# rom.net
KiCad netlist of a schematic drawn in EAGLE
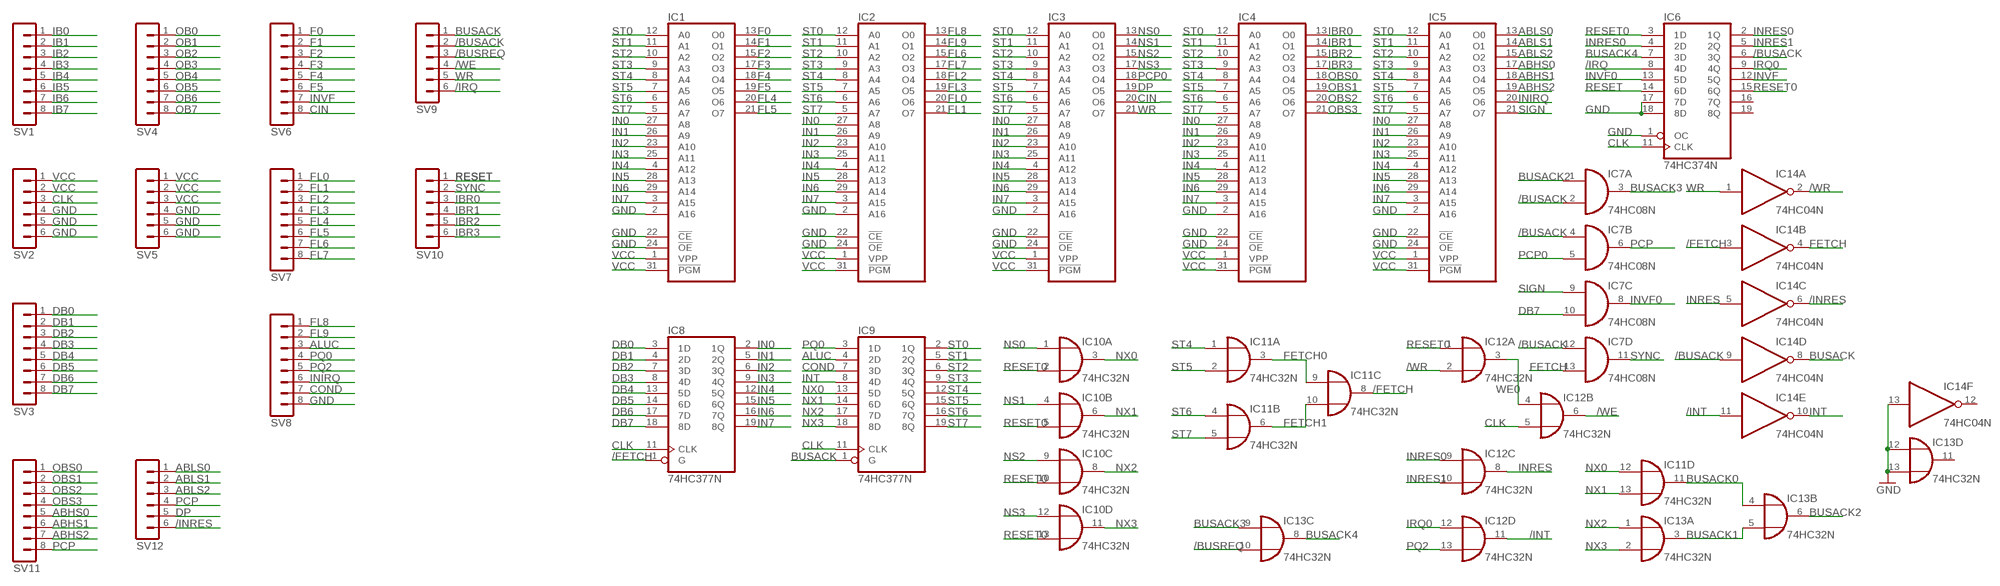
[diagram p0: schematic, sheet 1]

(export (version "E")
  (design (tool "Eeschema 10.0.6"))
  (components
    (comp (ref "IC1")
      (value "27010")
      (footprint "eagle-import:DIL32")
      (libsource (lib "eagle-import") (part "27010"))
    )
    (comp (ref "IC2")
      (value "27010")
      (footprint "eagle-import:DIL32")
      (libsource (lib "eagle-import") (part "27010"))
    )
    (comp (ref "IC3")
      (value "27010")
      (footprint "eagle-import:DIL32")
      (libsource (lib "eagle-import") (part "27010"))
    )
    (comp (ref "IC4")
      (value "27010")
      (footprint "eagle-import:DIL32")
      (libsource (lib "eagle-import") (part "27010"))
    )
    (comp (ref "IC5")
      (value "27010")
      (footprint "eagle-import:DIL32")
      (libsource (lib "eagle-import") (part "27010"))
    )
    (comp (ref "IC6")
      (value "74HC374N")
      (footprint "eagle-import:DIL20")
      (libsource (lib "eagle-import") (part "74374NHC"))
    )
    (comp (ref "IC7")
      (value "74HC08N")
      (footprint "eagle-import:DIL14")
      (libsource (lib "eagle-import") (part "7408NHC"))
    )
    (comp (ref "IC8")
      (value "74HC377N")
      (footprint "eagle-import:DIL20")
      (libsource (lib "eagle-import") (part "74377NHC"))
    )
    (comp (ref "IC9")
      (value "74HC377N")
      (footprint "eagle-import:DIL20")
      (libsource (lib "eagle-import") (part "74377NHC"))
    )
    (comp (ref "IC10")
      (value "74HC32N")
      (footprint "eagle-import:DIL14")
      (libsource (lib "eagle-import") (part "7432NHC"))
    )
    (comp (ref "IC11")
      (value "74HC32N")
      (footprint "eagle-import:DIL14")
      (libsource (lib "eagle-import") (part "7432NHC"))
    )
    (comp (ref "IC12")
      (value "74HC32N")
      (footprint "eagle-import:DIL14")
      (libsource (lib "eagle-import") (part "7432NHC"))
    )
    (comp (ref "IC13")
      (value "74HC32N")
      (footprint "eagle-import:DIL14")
      (libsource (lib "eagle-import") (part "7432NHC"))
    )
    (comp (ref "IC14")
      (value "74HC04N")
      (footprint "eagle-import:DIL14")
      (libsource (lib "eagle-import") (part "7404NHC"))
    )
    (comp (ref "SV1")
      (value "MA08-1")
      (footprint "eagle-import:MA08-1")
      (libsource (lib "eagle-import") (part "MA08-1"))
    )
    (comp (ref "SV2")
      (value "MA06-1")
      (footprint "eagle-import:MA06-1")
      (libsource (lib "eagle-import") (part "MA06-1"))
    )
    (comp (ref "SV3")
      (value "MA08-1")
      (footprint "eagle-import:MA08-1")
      (libsource (lib "eagle-import") (part "MA08-1"))
    )
    (comp (ref "SV4")
      (value "MA08-1")
      (footprint "eagle-import:MA08-1")
      (libsource (lib "eagle-import") (part "MA08-1"))
    )
    (comp (ref "SV5")
      (value "MA06-1")
      (footprint "eagle-import:MA06-1")
      (libsource (lib "eagle-import") (part "MA06-1"))
    )
    (comp (ref "SV6")
      (value "MA08-1")
      (footprint "eagle-import:MA08-1")
      (libsource (lib "eagle-import") (part "MA08-1"))
    )
    (comp (ref "SV7")
      (value "MA08-1")
      (footprint "eagle-import:MA08-1")
      (libsource (lib "eagle-import") (part "MA08-1"))
    )
    (comp (ref "SV8")
      (value "MA08-1")
      (footprint "eagle-import:MA08-1")
      (libsource (lib "eagle-import") (part "MA08-1"))
    )
    (comp (ref "SV9")
      (value "MA06-1")
      (footprint "eagle-import:MA06-1")
      (libsource (lib "eagle-import") (part "MA06-1"))
    )
    (comp (ref "SV10")
      (value "MA06-1")
      (footprint "eagle-import:MA06-1")
      (libsource (lib "eagle-import") (part "MA06-1"))
    )
    (comp (ref "SV11")
      (value "MA08-1")
      (footprint "eagle-import:MA08-1")
      (libsource (lib "eagle-import") (part "MA08-1"))
    )
    (comp (ref "SV12")
      (value "MA06-1")
      (footprint "eagle-import:MA06-1")
      (libsource (lib "eagle-import") (part "MA06-1"))
    )
  )
  (nets
    (net (code "1") (name "/ABHS0") (class "Default")
      (node (ref "IC5") (pin "17") (pinfunction "O3_17") (pintype "tri_state"))
      (node (ref "SV11") (pin "5") (pinfunction "5_5") (pintype "passive"))
    )
    (net (code "2") (name "/ABHS1") (class "Default")
      (node (ref "IC5") (pin "18") (pinfunction "O4_18") (pintype "tri_state"))
      (node (ref "SV11") (pin "6") (pinfunction "6_6") (pintype "passive"))
    )
    (net (code "3") (name "/ABHS2") (class "Default")
      (node (ref "IC5") (pin "19") (pinfunction "O5_19") (pintype "tri_state"))
      (node (ref "SV11") (pin "7") (pinfunction "7_7") (pintype "passive"))
    )
    (net (code "4") (name "/ABLS0") (class "Default")
      (node (ref "IC5") (pin "13") (pinfunction "O0_13") (pintype "tri_state"))
      (node (ref "SV12") (pin "1") (pinfunction "1_1") (pintype "passive"))
    )
    (net (code "5") (name "/ABLS1") (class "Default")
      (node (ref "IC5") (pin "14") (pinfunction "O1_14") (pintype "tri_state"))
      (node (ref "SV12") (pin "2") (pinfunction "2_2") (pintype "passive"))
    )
    (net (code "6") (name "/ABLS2") (class "Default")
      (node (ref "IC5") (pin "15") (pinfunction "O2_15") (pintype "tri_state"))
      (node (ref "SV12") (pin "3") (pinfunction "3_3") (pintype "passive"))
    )
    (net (code "7") (name "/ALUC") (class "Default")
      (node (ref "IC9") (pin "4") (pinfunction "2D_4") (pintype "input"))
      (node (ref "SV8") (pin "3") (pinfunction "3_3") (pintype "passive"))
    )
    (net (code "8") (name "/BUSACK") (class "Default")
      (node (ref "IC14") (pin "8") (pinfunction "O_8") (pintype "output"))
      (node (ref "IC9") (pin "1") (pinfunction "G_1") (pintype "input"))
      (node (ref "SV9") (pin "1") (pinfunction "1_1") (pintype "passive"))
    )
    (net (code "9") (name "/BUSACK0") (class "Default")
      (node (ref "IC11") (pin "11") (pinfunction "O_11") (pintype "output"))
      (node (ref "IC13") (pin "4") (pinfunction "I0_4") (pintype "input"))
    )
    (net (code "10") (name "/BUSACK1") (class "Default")
      (node (ref "IC13") (pin "3") (pinfunction "O_3") (pintype "output"))
      (node (ref "IC13") (pin "5") (pinfunction "I1_5") (pintype "input"))
    )
    (net (code "11") (name "/BUSACK2") (class "Default")
      (node (ref "IC13") (pin "6") (pinfunction "O_6") (pintype "output"))
      (node (ref "IC7") (pin "1") (pinfunction "I0_1") (pintype "input"))
    )
    (net (code "12") (name "/BUSACK3") (class "Default")
      (node (ref "IC13") (pin "9") (pinfunction "I0_9") (pintype "input"))
      (node (ref "IC7") (pin "3") (pinfunction "O_3") (pintype "output"))
    )
    (net (code "13") (name "/BUSACK4") (class "Default")
      (node (ref "IC13") (pin "8") (pinfunction "O_8") (pintype "output"))
      (node (ref "IC6") (pin "7") (pinfunction "3D_7") (pintype "input"))
    )
    (net (code "14") (name "/CIN") (class "Default")
      (node (ref "IC3") (pin "20") (pinfunction "O6_20") (pintype "tri_state"))
      (node (ref "SV6") (pin "8") (pinfunction "8_8") (pintype "passive"))
    )
    (net (code "15") (name "/CLK") (class "Default")
      (node (ref "IC12") (pin "5") (pinfunction "I1_5") (pintype "input"))
      (node (ref "IC6") (pin "11") (pinfunction "CLK_11") (pintype "input"))
      (node (ref "IC8") (pin "11") (pinfunction "CLK_11") (pintype "input"))
      (node (ref "IC9") (pin "11") (pinfunction "CLK_11") (pintype "input"))
      (node (ref "SV2") (pin "3") (pinfunction "3_3") (pintype "passive"))
    )
    (net (code "16") (name "/COND") (class "Default")
      (node (ref "IC9") (pin "7") (pinfunction "3D_7") (pintype "input"))
      (node (ref "SV8") (pin "7") (pinfunction "7_7") (pintype "passive"))
    )
    (net (code "17") (name "/DB0") (class "Default")
      (node (ref "IC8") (pin "3") (pinfunction "1D_3") (pintype "input"))
      (node (ref "SV3") (pin "1") (pinfunction "1_1") (pintype "passive"))
    )
    (net (code "18") (name "/DB1") (class "Default")
      (node (ref "IC8") (pin "4") (pinfunction "2D_4") (pintype "input"))
      (node (ref "SV3") (pin "2") (pinfunction "2_2") (pintype "passive"))
    )
    (net (code "19") (name "/DB2") (class "Default")
      (node (ref "IC8") (pin "7") (pinfunction "3D_7") (pintype "input"))
      (node (ref "SV3") (pin "3") (pinfunction "3_3") (pintype "passive"))
    )
    (net (code "20") (name "/DB3") (class "Default")
      (node (ref "IC8") (pin "8") (pinfunction "4D_8") (pintype "input"))
      (node (ref "SV3") (pin "4") (pinfunction "4_4") (pintype "passive"))
    )
    (net (code "21") (name "/DB4") (class "Default")
      (node (ref "IC8") (pin "13") (pinfunction "5D_13") (pintype "input"))
      (node (ref "SV3") (pin "5") (pinfunction "5_5") (pintype "passive"))
    )
    (net (code "22") (name "/DB5") (class "Default")
      (node (ref "IC8") (pin "14") (pinfunction "6D_14") (pintype "input"))
      (node (ref "SV3") (pin "6") (pinfunction "6_6") (pintype "passive"))
    )
    (net (code "23") (name "/DB6") (class "Default")
      (node (ref "IC8") (pin "17") (pinfunction "7D_17") (pintype "input"))
      (node (ref "SV3") (pin "7") (pinfunction "7_7") (pintype "passive"))
    )
    (net (code "24") (name "/DB7") (class "Default")
      (node (ref "IC7") (pin "10") (pinfunction "I1_10") (pintype "input"))
      (node (ref "IC8") (pin "18") (pinfunction "8D_18") (pintype "input"))
      (node (ref "SV3") (pin "8") (pinfunction "8_8") (pintype "passive"))
    )
    (net (code "25") (name "/DP") (class "Default")
      (node (ref "IC3") (pin "19") (pinfunction "O5_19") (pintype "tri_state"))
      (node (ref "SV12") (pin "5") (pinfunction "5_5") (pintype "passive"))
    )
    (net (code "26") (name "/F0") (class "Default")
      (node (ref "IC1") (pin "13") (pinfunction "O0_13") (pintype "tri_state"))
      (node (ref "SV6") (pin "1") (pinfunction "1_1") (pintype "passive"))
    )
    (net (code "27") (name "/F1") (class "Default")
      (node (ref "IC1") (pin "14") (pinfunction "O1_14") (pintype "tri_state"))
      (node (ref "SV6") (pin "2") (pinfunction "2_2") (pintype "passive"))
    )
    (net (code "28") (name "/F2") (class "Default")
      (node (ref "IC1") (pin "15") (pinfunction "O2_15") (pintype "tri_state"))
      (node (ref "SV6") (pin "3") (pinfunction "3_3") (pintype "passive"))
    )
    (net (code "29") (name "/F3") (class "Default")
      (node (ref "IC1") (pin "17") (pinfunction "O3_17") (pintype "tri_state"))
      (node (ref "SV6") (pin "4") (pinfunction "4_4") (pintype "passive"))
    )
    (net (code "30") (name "/F4") (class "Default")
      (node (ref "IC1") (pin "18") (pinfunction "O4_18") (pintype "tri_state"))
      (node (ref "SV6") (pin "5") (pinfunction "5_5") (pintype "passive"))
    )
    (net (code "31") (name "/F5") (class "Default")
      (node (ref "IC1") (pin "19") (pinfunction "O5_19") (pintype "tri_state"))
      (node (ref "SV6") (pin "6") (pinfunction "6_6") (pintype "passive"))
    )
    (net (code "32") (name "/FETCH") (class "Default")
      (node (ref "IC14") (pin "4") (pinfunction "O_4") (pintype "output"))
      (node (ref "IC7") (pin "13") (pinfunction "I1_13") (pintype "input"))
    )
    (net (code "33") (name "/FETCH0") (class "Default")
      (node (ref "IC11") (pin "3") (pinfunction "O_3") (pintype "output"))
      (node (ref "IC11") (pin "9") (pinfunction "I0_9") (pintype "input"))
    )
    (net (code "34") (name "/FETCH1") (class "Default")
      (node (ref "IC11") (pin "10") (pinfunction "I1_10") (pintype "input"))
      (node (ref "IC11") (pin "6") (pinfunction "O_6") (pintype "output"))
    )
    (net (code "35") (name "/FL0") (class "Default")
      (node (ref "IC2") (pin "20") (pinfunction "O6_20") (pintype "tri_state"))
      (node (ref "SV7") (pin "1") (pinfunction "1_1") (pintype "passive"))
    )
    (net (code "36") (name "/FL1") (class "Default")
      (node (ref "IC2") (pin "21") (pinfunction "O7_21") (pintype "tri_state"))
      (node (ref "SV7") (pin "2") (pinfunction "2_2") (pintype "passive"))
    )
    (net (code "37") (name "/FL2") (class "Default")
      (node (ref "IC2") (pin "18") (pinfunction "O4_18") (pintype "tri_state"))
      (node (ref "SV7") (pin "3") (pinfunction "3_3") (pintype "passive"))
    )
    (net (code "38") (name "/FL3") (class "Default")
      (node (ref "IC2") (pin "19") (pinfunction "O5_19") (pintype "tri_state"))
      (node (ref "SV7") (pin "4") (pinfunction "4_4") (pintype "passive"))
    )
    (net (code "39") (name "/FL4") (class "Default")
      (node (ref "IC1") (pin "20") (pinfunction "O6_20") (pintype "tri_state"))
      (node (ref "SV7") (pin "5") (pinfunction "5_5") (pintype "passive"))
    )
    (net (code "40") (name "/FL5") (class "Default")
      (node (ref "IC1") (pin "21") (pinfunction "O7_21") (pintype "tri_state"))
      (node (ref "SV7") (pin "6") (pinfunction "6_6") (pintype "passive"))
    )
    (net (code "41") (name "/FL6") (class "Default")
      (node (ref "IC2") (pin "15") (pinfunction "O2_15") (pintype "tri_state"))
      (node (ref "SV7") (pin "7") (pinfunction "7_7") (pintype "passive"))
    )
    (net (code "42") (name "/FL7") (class "Default")
      (node (ref "IC2") (pin "17") (pinfunction "O3_17") (pintype "tri_state"))
      (node (ref "SV7") (pin "8") (pinfunction "8_8") (pintype "passive"))
    )
    (net (code "43") (name "/FL8") (class "Default")
      (node (ref "IC2") (pin "13") (pinfunction "O0_13") (pintype "tri_state"))
      (node (ref "SV8") (pin "1") (pinfunction "1_1") (pintype "passive"))
    )
    (net (code "44") (name "/FL9") (class "Default")
      (node (ref "IC2") (pin "14") (pinfunction "O1_14") (pintype "tri_state"))
      (node (ref "SV8") (pin "2") (pinfunction "2_2") (pintype "passive"))
    )
    (net (code "45") (name "/IB0") (class "Default")
      (node (ref "SV1") (pin "1") (pinfunction "1_1") (pintype "passive"))
    )
    (net (code "46") (name "/IB1") (class "Default")
      (node (ref "SV1") (pin "2") (pinfunction "2_2") (pintype "passive"))
    )
    (net (code "47") (name "/IB2") (class "Default")
      (node (ref "SV1") (pin "3") (pinfunction "3_3") (pintype "passive"))
    )
    (net (code "48") (name "/IB3") (class "Default")
      (node (ref "SV1") (pin "4") (pinfunction "4_4") (pintype "passive"))
    )
    (net (code "49") (name "/IB4") (class "Default")
      (node (ref "SV1") (pin "5") (pinfunction "5_5") (pintype "passive"))
    )
    (net (code "50") (name "/IB5") (class "Default")
      (node (ref "SV1") (pin "6") (pinfunction "6_6") (pintype "passive"))
    )
    (net (code "51") (name "/IB6") (class "Default")
      (node (ref "SV1") (pin "7") (pinfunction "7_7") (pintype "passive"))
    )
    (net (code "52") (name "/IB7") (class "Default")
      (node (ref "SV1") (pin "8") (pinfunction "8_8") (pintype "passive"))
    )
    (net (code "53") (name "/IBR0") (class "Default")
      (node (ref "IC4") (pin "13") (pinfunction "O0_13") (pintype "tri_state"))
      (node (ref "SV10") (pin "3") (pinfunction "3_3") (pintype "passive"))
    )
    (net (code "54") (name "/IBR1") (class "Default")
      (node (ref "IC4") (pin "14") (pinfunction "O1_14") (pintype "tri_state"))
      (node (ref "SV10") (pin "4") (pinfunction "4_4") (pintype "passive"))
    )
    (net (code "55") (name "/IBR2") (class "Default")
      (node (ref "IC4") (pin "15") (pinfunction "O2_15") (pintype "tri_state"))
      (node (ref "SV10") (pin "5") (pinfunction "5_5") (pintype "passive"))
    )
    (net (code "56") (name "/IBR3") (class "Default")
      (node (ref "IC4") (pin "17") (pinfunction "O3_17") (pintype "tri_state"))
      (node (ref "SV10") (pin "6") (pinfunction "6_6") (pintype "passive"))
    )
    (net (code "57") (name "/IN0") (class "Default")
      (node (ref "IC1") (pin "27") (pinfunction "A8_27") (pintype "input"))
      (node (ref "IC2") (pin "27") (pinfunction "A8_27") (pintype "input"))
      (node (ref "IC3") (pin "27") (pinfunction "A8_27") (pintype "input"))
      (node (ref "IC4") (pin "27") (pinfunction "A8_27") (pintype "input"))
      (node (ref "IC5") (pin "27") (pinfunction "A8_27") (pintype "input"))
      (node (ref "IC8") (pin "2") (pinfunction "1Q_2") (pintype "output"))
    )
    (net (code "58") (name "/IN1") (class "Default")
      (node (ref "IC1") (pin "26") (pinfunction "A9_26") (pintype "input"))
      (node (ref "IC2") (pin "26") (pinfunction "A9_26") (pintype "input"))
      (node (ref "IC3") (pin "26") (pinfunction "A9_26") (pintype "input"))
      (node (ref "IC4") (pin "26") (pinfunction "A9_26") (pintype "input"))
      (node (ref "IC5") (pin "26") (pinfunction "A9_26") (pintype "input"))
      (node (ref "IC8") (pin "5") (pinfunction "2Q_5") (pintype "output"))
    )
    (net (code "59") (name "/IN2") (class "Default")
      (node (ref "IC1") (pin "23") (pinfunction "A10_23") (pintype "input"))
      (node (ref "IC2") (pin "23") (pinfunction "A10_23") (pintype "input"))
      (node (ref "IC3") (pin "23") (pinfunction "A10_23") (pintype "input"))
      (node (ref "IC4") (pin "23") (pinfunction "A10_23") (pintype "input"))
      (node (ref "IC5") (pin "23") (pinfunction "A10_23") (pintype "input"))
      (node (ref "IC8") (pin "6") (pinfunction "3Q_6") (pintype "output"))
    )
    (net (code "60") (name "/IN3") (class "Default")
      (node (ref "IC1") (pin "25") (pinfunction "A11_25") (pintype "input"))
      (node (ref "IC2") (pin "25") (pinfunction "A11_25") (pintype "input"))
      (node (ref "IC3") (pin "25") (pinfunction "A11_25") (pintype "input"))
      (node (ref "IC4") (pin "25") (pinfunction "A11_25") (pintype "input"))
      (node (ref "IC5") (pin "25") (pinfunction "A11_25") (pintype "input"))
      (node (ref "IC8") (pin "9") (pinfunction "4Q_9") (pintype "output"))
    )
    (net (code "61") (name "/IN4") (class "Default")
      (node (ref "IC1") (pin "4") (pinfunction "A12_4") (pintype "input"))
      (node (ref "IC2") (pin "4") (pinfunction "A12_4") (pintype "input"))
      (node (ref "IC3") (pin "4") (pinfunction "A12_4") (pintype "input"))
      (node (ref "IC4") (pin "4") (pinfunction "A12_4") (pintype "input"))
      (node (ref "IC5") (pin "4") (pinfunction "A12_4") (pintype "input"))
      (node (ref "IC8") (pin "12") (pinfunction "5Q_12") (pintype "output"))
    )
    (net (code "62") (name "/IN5") (class "Default")
      (node (ref "IC1") (pin "28") (pinfunction "A13_28") (pintype "input"))
      (node (ref "IC2") (pin "28") (pinfunction "A13_28") (pintype "input"))
      (node (ref "IC3") (pin "28") (pinfunction "A13_28") (pintype "input"))
      (node (ref "IC4") (pin "28") (pinfunction "A13_28") (pintype "input"))
      (node (ref "IC5") (pin "28") (pinfunction "A13_28") (pintype "input"))
      (node (ref "IC8") (pin "15") (pinfunction "6Q_15") (pintype "output"))
    )
    (net (code "63") (name "/IN6") (class "Default")
      (node (ref "IC1") (pin "29") (pinfunction "A14_29") (pintype "input"))
      (node (ref "IC2") (pin "29") (pinfunction "A14_29") (pintype "input"))
      (node (ref "IC3") (pin "29") (pinfunction "A14_29") (pintype "input"))
      (node (ref "IC4") (pin "29") (pinfunction "A14_29") (pintype "input"))
      (node (ref "IC5") (pin "29") (pinfunction "A14_29") (pintype "input"))
      (node (ref "IC8") (pin "16") (pinfunction "7Q_16") (pintype "output"))
    )
    (net (code "64") (name "/IN7") (class "Default")
      (node (ref "IC1") (pin "3") (pinfunction "A15_3") (pintype "input"))
      (node (ref "IC2") (pin "3") (pinfunction "A15_3") (pintype "input"))
      (node (ref "IC3") (pin "3") (pinfunction "A15_3") (pintype "input"))
      (node (ref "IC4") (pin "3") (pinfunction "A15_3") (pintype "input"))
      (node (ref "IC5") (pin "3") (pinfunction "A15_3") (pintype "input"))
      (node (ref "IC8") (pin "19") (pinfunction "8Q_19") (pintype "output"))
    )
    (net (code "65") (name "/INIRQ") (class "Default")
      (node (ref "IC5") (pin "20") (pinfunction "O6_20") (pintype "tri_state"))
      (node (ref "SV8") (pin "6") (pinfunction "6_6") (pintype "passive"))
    )
    (net (code "66") (name "/INRES") (class "Default")
      (node (ref "IC12") (pin "8") (pinfunction "O_8") (pintype "output"))
      (node (ref "IC14") (pin "5") (pinfunction "I_5") (pintype "input"))
    )
    (net (code "67") (name "/INRES0") (class "Default")
      (node (ref "IC12") (pin "9") (pinfunction "I0_9") (pintype "input"))
      (node (ref "IC6") (pin "2") (pinfunction "1Q_2") (pintype "tri_state"))
      (node (ref "IC6") (pin "4") (pinfunction "2D_4") (pintype "input"))
    )
    (net (code "68") (name "/INRES1") (class "Default")
      (node (ref "IC12") (pin "10") (pinfunction "I1_10") (pintype "input"))
      (node (ref "IC6") (pin "5") (pinfunction "2Q_5") (pintype "tri_state"))
    )
    (net (code "69") (name "/INT") (class "Default")
      (node (ref "IC14") (pin "10") (pinfunction "O_10") (pintype "output"))
      (node (ref "IC9") (pin "8") (pinfunction "4D_8") (pintype "input"))
    )
    (net (code "70") (name "/INVF") (class "Default")
      (node (ref "IC6") (pin "12") (pinfunction "5Q_12") (pintype "tri_state"))
      (node (ref "SV6") (pin "7") (pinfunction "7_7") (pintype "passive"))
    )
    (net (code "71") (name "/INVF0") (class "Default")
      (node (ref "IC6") (pin "13") (pinfunction "5D_13") (pintype "input"))
      (node (ref "IC7") (pin "8") (pinfunction "O_8") (pintype "output"))
    )
    (net (code "72") (name "/IRQ0") (class "Default")
      (node (ref "IC12") (pin "12") (pinfunction "I0_12") (pintype "input"))
      (node (ref "IC6") (pin "9") (pinfunction "4Q_9") (pintype "tri_state"))
    )
    (net (code "73") (name "/NS0") (class "Default")
      (node (ref "IC10") (pin "1") (pinfunction "I0_1") (pintype "input"))
      (node (ref "IC3") (pin "13") (pinfunction "O0_13") (pintype "tri_state"))
    )
    (net (code "74") (name "/NS1") (class "Default")
      (node (ref "IC10") (pin "4") (pinfunction "I0_4") (pintype "input"))
      (node (ref "IC3") (pin "14") (pinfunction "O1_14") (pintype "tri_state"))
    )
    (net (code "75") (name "/NS2") (class "Default")
      (node (ref "IC10") (pin "9") (pinfunction "I0_9") (pintype "input"))
      (node (ref "IC3") (pin "15") (pinfunction "O2_15") (pintype "tri_state"))
    )
    (net (code "76") (name "/NS3") (class "Default")
      (node (ref "IC10") (pin "12") (pinfunction "I0_12") (pintype "input"))
      (node (ref "IC3") (pin "17") (pinfunction "O3_17") (pintype "tri_state"))
    )
    (net (code "77") (name "/NX0") (class "Default")
      (node (ref "IC10") (pin "3") (pinfunction "O_3") (pintype "output"))
      (node (ref "IC11") (pin "12") (pinfunction "I0_12") (pintype "input"))
      (node (ref "IC9") (pin "13") (pinfunction "5D_13") (pintype "input"))
    )
    (net (code "78") (name "/NX1") (class "Default")
      (node (ref "IC10") (pin "6") (pinfunction "O_6") (pintype "output"))
      (node (ref "IC11") (pin "13") (pinfunction "I1_13") (pintype "input"))
      (node (ref "IC9") (pin "14") (pinfunction "6D_14") (pintype "input"))
    )
    (net (code "79") (name "/NX2") (class "Default")
      (node (ref "IC10") (pin "8") (pinfunction "O_8") (pintype "output"))
      (node (ref "IC13") (pin "1") (pinfunction "I0_1") (pintype "input"))
      (node (ref "IC9") (pin "17") (pinfunction "7D_17") (pintype "input"))
    )
    (net (code "80") (name "/NX3") (class "Default")
      (node (ref "IC10") (pin "11") (pinfunction "O_11") (pintype "output"))
      (node (ref "IC13") (pin "2") (pinfunction "I1_2") (pintype "input"))
      (node (ref "IC9") (pin "18") (pinfunction "8D_18") (pintype "input"))
    )
    (net (code "81") (name "/OB0") (class "Default")
      (node (ref "SV4") (pin "1") (pinfunction "1_1") (pintype "passive"))
    )
    (net (code "82") (name "/OB1") (class "Default")
      (node (ref "SV4") (pin "2") (pinfunction "2_2") (pintype "passive"))
    )
    (net (code "83") (name "/OB2") (class "Default")
      (node (ref "SV4") (pin "3") (pinfunction "3_3") (pintype "passive"))
    )
    (net (code "84") (name "/OB3") (class "Default")
      (node (ref "SV4") (pin "4") (pinfunction "4_4") (pintype "passive"))
    )
    (net (code "85") (name "/OB4") (class "Default")
      (node (ref "SV4") (pin "5") (pinfunction "5_5") (pintype "passive"))
    )
    (net (code "86") (name "/OB5") (class "Default")
      (node (ref "SV4") (pin "6") (pinfunction "6_6") (pintype "passive"))
    )
    (net (code "87") (name "/OB6") (class "Default")
      (node (ref "SV4") (pin "7") (pinfunction "7_7") (pintype "passive"))
    )
    (net (code "88") (name "/OB7") (class "Default")
      (node (ref "SV4") (pin "8") (pinfunction "8_8") (pintype "passive"))
    )
    (net (code "89") (name "/OBS0") (class "Default")
      (node (ref "IC4") (pin "18") (pinfunction "O4_18") (pintype "tri_state"))
      (node (ref "SV11") (pin "1") (pinfunction "1_1") (pintype "passive"))
    )
    (net (code "90") (name "/OBS1") (class "Default")
      (node (ref "IC4") (pin "19") (pinfunction "O5_19") (pintype "tri_state"))
      (node (ref "SV11") (pin "2") (pinfunction "2_2") (pintype "passive"))
    )
    (net (code "91") (name "/OBS2") (class "Default")
      (node (ref "IC4") (pin "20") (pinfunction "O6_20") (pintype "tri_state"))
      (node (ref "SV11") (pin "3") (pinfunction "3_3") (pintype "passive"))
    )
    (net (code "92") (name "/OBS3") (class "Default")
      (node (ref "IC4") (pin "21") (pinfunction "O7_21") (pintype "tri_state"))
      (node (ref "SV11") (pin "4") (pinfunction "4_4") (pintype "passive"))
    )
    (net (code "93") (name "/PCP") (class "Default")
      (node (ref "IC7") (pin "6") (pinfunction "O_6") (pintype "output"))
      (node (ref "SV11") (pin "8") (pinfunction "8_8") (pintype "passive"))
      (node (ref "SV12") (pin "4") (pinfunction "4_4") (pintype "passive"))
    )
    (net (code "94") (name "/PCP0") (class "Default")
      (node (ref "IC3") (pin "18") (pinfunction "O4_18") (pintype "tri_state"))
      (node (ref "IC7") (pin "5") (pinfunction "I1_5") (pintype "input"))
    )
    (net (code "95") (name "/PQ0") (class "Default")
      (node (ref "IC9") (pin "3") (pinfunction "1D_3") (pintype "input"))
      (node (ref "SV8") (pin "4") (pinfunction "4_4") (pintype "passive"))
    )
    (net (code "96") (name "/PQ2") (class "Default")
      (node (ref "IC12") (pin "13") (pinfunction "I1_13") (pintype "input"))
      (node (ref "SV8") (pin "5") (pinfunction "5_5") (pintype "passive"))
    )
    (net (code "97") (name "/RESET") (class "Default")
      (node (ref "IC6") (pin "14") (pinfunction "6D_14") (pintype "input"))
      (node (ref "SV10") (pin "1") (pinfunction "1_1") (pintype "passive"))
    )
    (net (code "98") (name "/RESET0") (class "Default")
      (node (ref "IC10") (pin "10") (pinfunction "I1_10") (pintype "input"))
      (node (ref "IC10") (pin "13") (pinfunction "I1_13") (pintype "input"))
      (node (ref "IC10") (pin "2") (pinfunction "I1_2") (pintype "input"))
      (node (ref "IC10") (pin "5") (pinfunction "I1_5") (pintype "input"))
      (node (ref "IC12") (pin "1") (pinfunction "I0_1") (pintype "input"))
      (node (ref "IC6") (pin "15") (pinfunction "6Q_15") (pintype "tri_state"))
      (node (ref "IC6") (pin "3") (pinfunction "1D_3") (pintype "input"))
    )
    (net (code "99") (name "/SIGN") (class "Default")
      (node (ref "IC5") (pin "21") (pinfunction "O7_21") (pintype "tri_state"))
      (node (ref "IC7") (pin "9") (pinfunction "I0_9") (pintype "input"))
    )
    (net (code "100") (name "/ST0") (class "Default")
      (node (ref "IC1") (pin "12") (pinfunction "A0_12") (pintype "input"))
      (node (ref "IC2") (pin "12") (pinfunction "A0_12") (pintype "input"))
      (node (ref "IC3") (pin "12") (pinfunction "A0_12") (pintype "input"))
      (node (ref "IC4") (pin "12") (pinfunction "A0_12") (pintype "input"))
      (node (ref "IC5") (pin "12") (pinfunction "A0_12") (pintype "input"))
      (node (ref "IC9") (pin "2") (pinfunction "1Q_2") (pintype "output"))
    )
    (net (code "101") (name "/ST1") (class "Default")
      (node (ref "IC1") (pin "11") (pinfunction "A1_11") (pintype "input"))
      (node (ref "IC2") (pin "11") (pinfunction "A1_11") (pintype "input"))
      (node (ref "IC3") (pin "11") (pinfunction "A1_11") (pintype "input"))
      (node (ref "IC4") (pin "11") (pinfunction "A1_11") (pintype "input"))
      (node (ref "IC5") (pin "11") (pinfunction "A1_11") (pintype "input"))
      (node (ref "IC9") (pin "5") (pinfunction "2Q_5") (pintype "output"))
    )
    (net (code "102") (name "/ST2") (class "Default")
      (node (ref "IC1") (pin "10") (pinfunction "A2_10") (pintype "input"))
      (node (ref "IC2") (pin "10") (pinfunction "A2_10") (pintype "input"))
      (node (ref "IC3") (pin "10") (pinfunction "A2_10") (pintype "input"))
      (node (ref "IC4") (pin "10") (pinfunction "A2_10") (pintype "input"))
      (node (ref "IC5") (pin "10") (pinfunction "A2_10") (pintype "input"))
      (node (ref "IC9") (pin "6") (pinfunction "3Q_6") (pintype "output"))
    )
    (net (code "103") (name "/ST3") (class "Default")
      (node (ref "IC1") (pin "9") (pinfunction "A3_9") (pintype "input"))
      (node (ref "IC2") (pin "9") (pinfunction "A3_9") (pintype "input"))
      (node (ref "IC3") (pin "9") (pinfunction "A3_9") (pintype "input"))
      (node (ref "IC4") (pin "9") (pinfunction "A3_9") (pintype "input"))
      (node (ref "IC5") (pin "9") (pinfunction "A3_9") (pintype "input"))
      (node (ref "IC9") (pin "9") (pinfunction "4Q_9") (pintype "output"))
    )
    (net (code "104") (name "/ST4") (class "Default")
      (node (ref "IC1") (pin "8") (pinfunction "A4_8") (pintype "input"))
      (node (ref "IC11") (pin "1") (pinfunction "I0_1") (pintype "input"))
      (node (ref "IC2") (pin "8") (pinfunction "A4_8") (pintype "input"))
      (node (ref "IC3") (pin "8") (pinfunction "A4_8") (pintype "input"))
      (node (ref "IC4") (pin "8") (pinfunction "A4_8") (pintype "input"))
      (node (ref "IC5") (pin "8") (pinfunction "A4_8") (pintype "input"))
      (node (ref "IC9") (pin "12") (pinfunction "5Q_12") (pintype "output"))
    )
    (net (code "105") (name "/ST5") (class "Default")
      (node (ref "IC1") (pin "7") (pinfunction "A5_7") (pintype "input"))
      (node (ref "IC11") (pin "2") (pinfunction "I1_2") (pintype "input"))
      (node (ref "IC2") (pin "7") (pinfunction "A5_7") (pintype "input"))
      (node (ref "IC3") (pin "7") (pinfunction "A5_7") (pintype "input"))
      (node (ref "IC4") (pin "7") (pinfunction "A5_7") (pintype "input"))
      (node (ref "IC5") (pin "7") (pinfunction "A5_7") (pintype "input"))
      (node (ref "IC9") (pin "15") (pinfunction "6Q_15") (pintype "output"))
    )
    (net (code "106") (name "/ST6") (class "Default")
      (node (ref "IC1") (pin "6") (pinfunction "A6_6") (pintype "input"))
      (node (ref "IC11") (pin "4") (pinfunction "I0_4") (pintype "input"))
      (node (ref "IC2") (pin "6") (pinfunction "A6_6") (pintype "input"))
      (node (ref "IC3") (pin "6") (pinfunction "A6_6") (pintype "input"))
      (node (ref "IC4") (pin "6") (pinfunction "A6_6") (pintype "input"))
      (node (ref "IC5") (pin "6") (pinfunction "A6_6") (pintype "input"))
      (node (ref "IC9") (pin "16") (pinfunction "7Q_16") (pintype "output"))
    )
    (net (code "107") (name "/ST7") (class "Default")
      (node (ref "IC1") (pin "5") (pinfunction "A7_5") (pintype "input"))
      (node (ref "IC11") (pin "5") (pinfunction "I1_5") (pintype "input"))
      (node (ref "IC2") (pin "5") (pinfunction "A7_5") (pintype "input"))
      (node (ref "IC3") (pin "5") (pinfunction "A7_5") (pintype "input"))
      (node (ref "IC4") (pin "5") (pinfunction "A7_5") (pintype "input"))
      (node (ref "IC5") (pin "5") (pinfunction "A7_5") (pintype "input"))
      (node (ref "IC9") (pin "19") (pinfunction "8Q_19") (pintype "output"))
    )
    (net (code "108") (name "/SYNC") (class "Default")
      (node (ref "IC7") (pin "11") (pinfunction "O_11") (pintype "output"))
      (node (ref "SV10") (pin "2") (pinfunction "2_2") (pintype "passive"))
    )
    (net (code "109") (name "/VCC") (class "Default")
      (node (ref "IC1") (pin "1") (pinfunction "VPP_1") (pintype "input"))
      (node (ref "IC1") (pin "31") (pinfunction "~{PGM}_31") (pintype "input"))
      (node (ref "IC2") (pin "1") (pinfunction "VPP_1") (pintype "input"))
      (node (ref "IC2") (pin "31") (pinfunction "~{PGM}_31") (pintype "input"))
      (node (ref "IC3") (pin "1") (pinfunction "VPP_1") (pintype "input"))
      (node (ref "IC3") (pin "31") (pinfunction "~{PGM}_31") (pintype "input"))
      (node (ref "IC4") (pin "1") (pinfunction "VPP_1") (pintype "input"))
      (node (ref "IC4") (pin "31") (pinfunction "~{PGM}_31") (pintype "input"))
      (node (ref "IC5") (pin "1") (pinfunction "VPP_1") (pintype "input"))
      (node (ref "IC5") (pin "31") (pinfunction "~{PGM}_31") (pintype "input"))
      (node (ref "SV2") (pin "1") (pinfunction "1_1") (pintype "passive"))
      (node (ref "SV2") (pin "2") (pinfunction "2_2") (pintype "passive"))
      (node (ref "SV5") (pin "1") (pinfunction "1_1") (pintype "passive"))
      (node (ref "SV5") (pin "2") (pinfunction "2_2") (pintype "passive"))
      (node (ref "SV5") (pin "3") (pinfunction "3_3") (pintype "passive"))
    )
    (net (code "110") (name "/WE0") (class "Default")
      (node (ref "IC12") (pin "3") (pinfunction "O_3") (pintype "output"))
      (node (ref "IC12") (pin "4") (pinfunction "I0_4") (pintype "input"))
    )
    (net (code "111") (name "/WR") (class "Default")
      (node (ref "IC14") (pin "1") (pinfunction "I_1") (pintype "input"))
      (node (ref "IC3") (pin "21") (pinfunction "O7_21") (pintype "tri_state"))
      (node (ref "SV9") (pin "5") (pinfunction "5_5") (pintype "passive"))
    )
    (net (code "112") (name "/{slash}BUSACK") (class "Default")
      (node (ref "IC14") (pin "9") (pinfunction "I_9") (pintype "input"))
      (node (ref "IC6") (pin "6") (pinfunction "3Q_6") (pintype "tri_state"))
      (node (ref "IC7") (pin "12") (pinfunction "I0_12") (pintype "input"))
      (node (ref "IC7") (pin "2") (pinfunction "I1_2") (pintype "input"))
      (node (ref "IC7") (pin "4") (pinfunction "I0_4") (pintype "input"))
      (node (ref "SV9") (pin "2") (pinfunction "2_2") (pintype "passive"))
    )
    (net (code "113") (name "/{slash}BUSREQ") (class "Default")
      (node (ref "IC13") (pin "10") (pinfunction "I1_10") (pintype "input"))
      (node (ref "SV9") (pin "3") (pinfunction "3_3") (pintype "passive"))
    )
    (net (code "114") (name "/{slash}FETCH") (class "Default")
      (node (ref "IC11") (pin "8") (pinfunction "O_8") (pintype "output"))
      (node (ref "IC14") (pin "3") (pinfunction "I_3") (pintype "input"))
      (node (ref "IC8") (pin "1") (pinfunction "G_1") (pintype "input"))
    )
    (net (code "115") (name "/{slash}INRES") (class "Default")
      (node (ref "IC14") (pin "6") (pinfunction "O_6") (pintype "output"))
      (node (ref "SV12") (pin "6") (pinfunction "6_6") (pintype "passive"))
    )
    (net (code "116") (name "/{slash}INT") (class "Default")
      (node (ref "IC12") (pin "11") (pinfunction "O_11") (pintype "output"))
      (node (ref "IC14") (pin "11") (pinfunction "I_11") (pintype "input"))
    )
    (net (code "117") (name "/{slash}IRQ") (class "Default")
      (node (ref "IC6") (pin "8") (pinfunction "4D_8") (pintype "input"))
      (node (ref "SV9") (pin "6") (pinfunction "6_6") (pintype "passive"))
    )
    (net (code "118") (name "/{slash}WE") (class "Default")
      (node (ref "IC12") (pin "6") (pinfunction "O_6") (pintype "output"))
      (node (ref "SV9") (pin "4") (pinfunction "4_4") (pintype "passive"))
    )
    (net (code "119") (name "/{slash}WR") (class "Default")
      (node (ref "IC12") (pin "2") (pinfunction "I1_2") (pintype "input"))
      (node (ref "IC14") (pin "2") (pinfunction "O_2") (pintype "output"))
    )
    (net (code "120") (name "GND") (class "Default")
      (node (ref "IC1") (pin "2") (pinfunction "A16_2") (pintype "input"))
      (node (ref "IC1") (pin "22") (pinfunction "~{CE}_22") (pintype "input"))
      (node (ref "IC1") (pin "24") (pinfunction "~{OE}_24") (pintype "input"))
      (node (ref "IC13") (pin "12") (pinfunction "I0_12") (pintype "input"))
      (node (ref "IC13") (pin "13") (pinfunction "I1_13") (pintype "input"))
      (node (ref "IC14") (pin "13") (pinfunction "I_13") (pintype "input"))
      (node (ref "IC2") (pin "2") (pinfunction "A16_2") (pintype "input"))
      (node (ref "IC2") (pin "22") (pinfunction "~{CE}_22") (pintype "input"))
      (node (ref "IC2") (pin "24") (pinfunction "~{OE}_24") (pintype "input"))
      (node (ref "IC3") (pin "2") (pinfunction "A16_2") (pintype "input"))
      (node (ref "IC3") (pin "22") (pinfunction "~{CE}_22") (pintype "input"))
      (node (ref "IC3") (pin "24") (pinfunction "~{OE}_24") (pintype "input"))
      (node (ref "IC4") (pin "2") (pinfunction "A16_2") (pintype "input"))
      (node (ref "IC4") (pin "22") (pinfunction "~{CE}_22") (pintype "input"))
      (node (ref "IC4") (pin "24") (pinfunction "~{OE}_24") (pintype "input"))
      (node (ref "IC5") (pin "2") (pinfunction "A16_2") (pintype "input"))
      (node (ref "IC5") (pin "22") (pinfunction "~{CE}_22") (pintype "input"))
      (node (ref "IC5") (pin "24") (pinfunction "~{OE}_24") (pintype "input"))
      (node (ref "IC6") (pin "1") (pinfunction "OC_1") (pintype "input"))
      (node (ref "IC6") (pin "17") (pinfunction "7D_17") (pintype "input"))
      (node (ref "IC6") (pin "18") (pinfunction "8D_18") (pintype "input"))
      (node (ref "SV2") (pin "4") (pinfunction "4_4") (pintype "passive"))
      (node (ref "SV2") (pin "5") (pinfunction "5_5") (pintype "passive"))
      (node (ref "SV2") (pin "6") (pinfunction "6_6") (pintype "passive"))
      (node (ref "SV5") (pin "4") (pinfunction "4_4") (pintype "passive"))
      (node (ref "SV5") (pin "5") (pinfunction "5_5") (pintype "passive"))
      (node (ref "SV5") (pin "6") (pinfunction "6_6") (pintype "passive"))
      (node (ref "SV8") (pin "8") (pinfunction "8_8") (pintype "passive"))
    )
    (net (code "121") (name "unconnected-(IC6A-7Q-Pad16)") (class "Default")
      (node (ref "IC6") (pin "16") (pinfunction "7Q_16") (pintype "tri_state"))
    )
    (net (code "122") (name "unconnected-(IC6A-8Q-Pad19)") (class "Default")
      (node (ref "IC6") (pin "19") (pinfunction "8Q_19") (pintype "tri_state"))
    )
    (net (code "123") (name "unconnected-(IC13D-O-Pad11)") (class "Default")
      (node (ref "IC13") (pin "11") (pinfunction "O_11") (pintype "output"))
    )
    (net (code "124") (name "unconnected-(IC14F-O-Pad12)") (class "Default")
      (node (ref "IC14") (pin "12") (pinfunction "O_12") (pintype "output"))
    )
  )
)
